# CW308T_LPC1343_CONN.net
KiCad netlist of a schematic drawn in Altium Designer
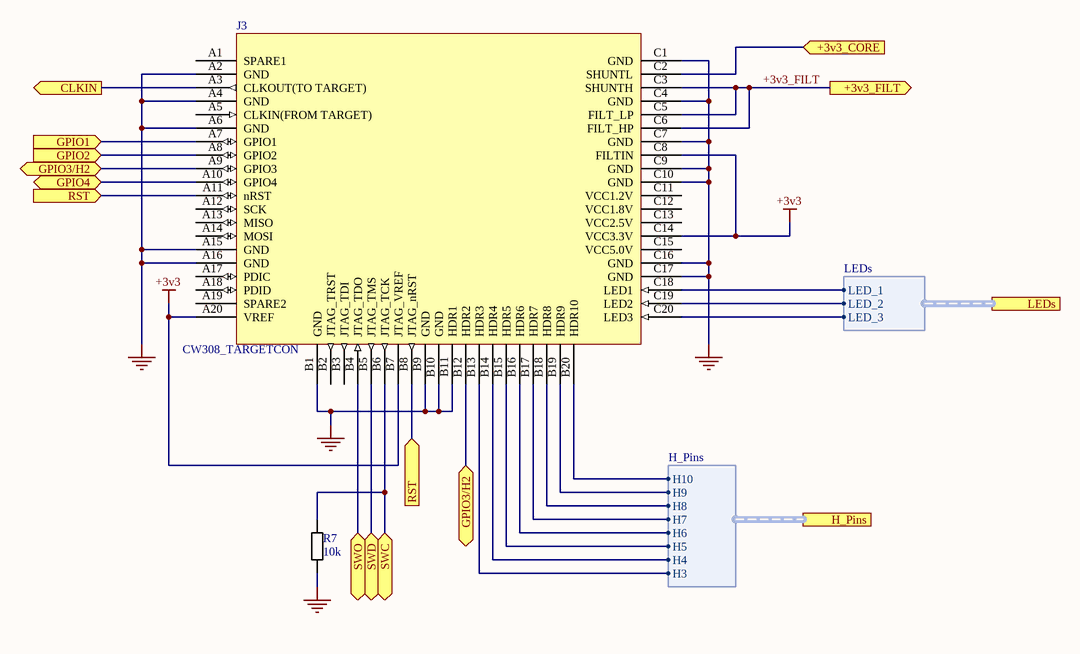
[diagram p0: CW308T_LPC1343_CONN.SchDoc]

(export (version "E")
  (design (tool "Eeschema 10.0.6"))
  (components
    (comp (ref "J3")
      (value "CW308_TARGETCON")
      (footprint "CW308_TBOARD_CONN")
      (description "CW308 \"Standard\" Target Board Connector")
      (fields (field (name "PART NUMBER") "CW308_TBOARD"))
      (libsource (lib "NewAE_AltiumLib") (part "CW308_TBOARD"))
    )
    (comp (ref "R7")
      (value "10k")
      (footprint "RESC1608X55N")
      (description "10k res, 0603, 1%, 1/10W")
      (fields (field (name "PART NUMBER") "RCHIP-10K-0603") (field (name "TOLERANCE") "1%"))
      (libsource (lib "NewAE_AltiumLib") (part "RES-EU"))
    )
  )
  (nets
    (net (code "3") (name "+3v3") (class "Default")
      (node (ref "J3") (pin "A20") (pinfunction "VREF_A20") (pintype "tri_state"))
      (node (ref "J3") (pin "B7") (pinfunction "JTAG_VREF_B7") (pintype "tri_state"))
      (node (ref "J3") (pin "C14") (pinfunction "VCC3.3V_C14") (pintype "power_in"))
      (node (ref "J3") (pin "C8") (pinfunction "FILTIN_C8") (pintype "passive"))
    )
    (net (code "4") (name "/+3v3_CORE") (class "Default")
      (node (ref "J3") (pin "C2") (pinfunction "SHUNTL_C2") (pintype "passive"))
    )
    (net (code "5") (name "/+3v3_FILT") (class "Default")
      (node (ref "J3") (pin "C3") (pinfunction "SHUNTH_C3") (pintype "passive"))
      (node (ref "J3") (pin "C5") (pinfunction "FILT_LP_C5") (pintype "passive"))
      (node (ref "J3") (pin "C6") (pinfunction "FILT_HP_C6") (pintype "passive"))
    )
    (net (code "6") (name "/CLKIN") (class "Default")
      (node (ref "J3") (pin "A3") (pinfunction "CLKOUT(TO_TARGET)_A3") (pintype "output"))
    )
    (net (code "7") (name "/GPIO1") (class "Default")
      (node (ref "J3") (pin "A7") (pinfunction "GPIO1_A7") (pintype "bidirectional"))
    )
    (net (code "8") (name "/GPIO2") (class "Default")
      (node (ref "J3") (pin "A8") (pinfunction "GPIO2_A8") (pintype "bidirectional"))
    )
    (net (code "9") (name "/GPIO3{slash}H2") (class "Default")
      (node (ref "J3") (pin "A9") (pinfunction "GPIO3_A9") (pintype "bidirectional"))
      (node (ref "J3") (pin "B12") (pinfunction "HDR2_B12") (pintype "passive"))
    )
    (net (code "10") (name "/GPIO4") (class "Default")
      (node (ref "J3") (pin "A10") (pinfunction "GPIO4_A10") (pintype "bidirectional"))
    )
    (net (code "11") (name "/H3") (class "Default")
      (node (ref "J3") (pin "B13") (pinfunction "HDR3_B13") (pintype "passive"))
    )
    (net (code "12") (name "/H4") (class "Default")
      (node (ref "J3") (pin "B14") (pinfunction "HDR4_B14") (pintype "passive"))
    )
    (net (code "13") (name "/H5") (class "Default")
      (node (ref "J3") (pin "B15") (pinfunction "HDR5_B15") (pintype "passive"))
    )
    (net (code "14") (name "/H6") (class "Default")
      (node (ref "J3") (pin "B16") (pinfunction "HDR6_B16") (pintype "passive"))
    )
    (net (code "15") (name "/H7") (class "Default")
      (node (ref "J3") (pin "B17") (pinfunction "HDR7_B17") (pintype "passive"))
    )
    (net (code "16") (name "/H8") (class "Default")
      (node (ref "J3") (pin "B18") (pinfunction "HDR8_B18") (pintype "passive"))
    )
    (net (code "17") (name "/H9") (class "Default")
      (node (ref "J3") (pin "B19") (pinfunction "HDR9_B19") (pintype "passive"))
    )
    (net (code "18") (name "/H10") (class "Default")
      (node (ref "J3") (pin "B20") (pinfunction "HDR10_B20") (pintype "passive"))
    )
    (net (code "19") (name "/LED_1") (class "Default")
      (node (ref "J3") (pin "C18") (pinfunction "LED1_C18") (pintype "input"))
    )
    (net (code "20") (name "/LED_2") (class "Default")
      (node (ref "J3") (pin "C19") (pinfunction "LED2_C19") (pintype "input"))
    )
    (net (code "21") (name "/LED_3") (class "Default")
      (node (ref "J3") (pin "C20") (pinfunction "LED3_C20") (pintype "input"))
    )
    (net (code "22") (name "/RST") (class "Default")
      (node (ref "J3") (pin "A11") (pinfunction "nRST_A11") (pintype "bidirectional"))
      (node (ref "J3") (pin "B8") (pinfunction "JTAG_nRST_B8") (pintype "output"))
    )
    (net (code "23") (name "/SWC") (class "Default")
      (node (ref "J3") (pin "B6") (pinfunction "JTAG_TCK_B6") (pintype "output"))
      (node (ref "R7") (pin "1") (pinfunction "1_1") (pintype "passive"))
    )
    (net (code "24") (name "/SWD") (class "Default")
      (node (ref "J3") (pin "B5") (pinfunction "JTAG_TMS_B5") (pintype "output"))
    )
    (net (code "25") (name "/SWO") (class "Default")
      (node (ref "J3") (pin "B4") (pinfunction "JTAG_TDO_B4") (pintype "input"))
    )
    (net (code "28") (name "GND") (class "Default")
      (node (ref "J3") (pin "A15") (pinfunction "GND_A15") (pintype "passive"))
      (node (ref "J3") (pin "A16") (pinfunction "GND_A16") (pintype "passive"))
      (node (ref "J3") (pin "A2") (pinfunction "GND_A2") (pintype "passive"))
      (node (ref "J3") (pin "A4") (pinfunction "GND_A4") (pintype "passive"))
      (node (ref "J3") (pin "A6") (pinfunction "GND_A6") (pintype "power_in"))
      (node (ref "J3") (pin "B1") (pinfunction "GND_B1") (pintype "passive"))
      (node (ref "J3") (pin "B10") (pinfunction "GND_B10") (pintype "passive"))
      (node (ref "J3") (pin "B11") (pinfunction "HDR1_B11") (pintype "passive"))
      (node (ref "J3") (pin "B9") (pinfunction "GND_B9") (pintype "passive"))
      (node (ref "J3") (pin "C1") (pinfunction "GND_C1") (pintype "power_in"))
      (node (ref "J3") (pin "C10") (pinfunction "GND_C10") (pintype "power_in"))
      (node (ref "J3") (pin "C16") (pinfunction "GND_C16") (pintype "power_in"))
      (node (ref "J3") (pin "C17") (pinfunction "GND_C17") (pintype "power_in"))
      (node (ref "J3") (pin "C4") (pinfunction "GND_C4") (pintype "power_in"))
      (node (ref "J3") (pin "C7") (pinfunction "GND_C7") (pintype "power_in"))
      (node (ref "J3") (pin "C9") (pinfunction "GND_C9") (pintype "power_in"))
      (node (ref "R7") (pin "2") (pinfunction "2_2") (pintype "passive"))
    )
    (net (code "29") (name "unconnected-(J3-CLKIN(FROM_TARGET)-PadA5)") (class "Default")
      (node (ref "J3") (pin "A5") (pinfunction "CLKIN(FROM_TARGET)_A5") (pintype "input"))
    )
    (net (code "30") (name "unconnected-(J3-JTAG_TDI-PadB3)") (class "Default")
      (node (ref "J3") (pin "B3") (pinfunction "JTAG_TDI_B3") (pintype "output"))
    )
    (net (code "31") (name "unconnected-(J3-JTAG_TRST-PadB2)") (class "Default")
      (node (ref "J3") (pin "B2") (pinfunction "JTAG_TRST_B2") (pintype "output"))
    )
    (net (code "32") (name "unconnected-(J3-MISO-PadA13)") (class "Default")
      (node (ref "J3") (pin "A13") (pinfunction "MISO_A13") (pintype "bidirectional"))
    )
    (net (code "33") (name "unconnected-(J3-MOSI-PadA14)") (class "Default")
      (node (ref "J3") (pin "A14") (pinfunction "MOSI_A14") (pintype "bidirectional"))
    )
    (net (code "34") (name "unconnected-(J3-PDIC-PadA17)") (class "Default")
      (node (ref "J3") (pin "A17") (pinfunction "PDIC_A17") (pintype "bidirectional"))
    )
    (net (code "35") (name "unconnected-(J3-PDID-PadA18)") (class "Default")
      (node (ref "J3") (pin "A18") (pinfunction "PDID_A18") (pintype "bidirectional"))
    )
    (net (code "36") (name "unconnected-(J3-SCK-PadA12)") (class "Default")
      (node (ref "J3") (pin "A12") (pinfunction "SCK_A12") (pintype "bidirectional"))
    )
    (net (code "37") (name "unconnected-(J3-SPARE1-PadA1)") (class "Default")
      (node (ref "J3") (pin "A1") (pinfunction "SPARE1_A1") (pintype "passive"))
    )
    (net (code "38") (name "unconnected-(J3-SPARE2-PadA19)") (class "Default")
      (node (ref "J3") (pin "A19") (pinfunction "SPARE2_A19") (pintype "passive"))
    )
    (net (code "39") (name "unconnected-(J3-VCC1.2V-PadC11)") (class "Default")
      (node (ref "J3") (pin "C11") (pinfunction "VCC1.2V_C11") (pintype "power_in"))
    )
    (net (code "40") (name "unconnected-(J3-VCC1.8V-PadC12)") (class "Default")
      (node (ref "J3") (pin "C12") (pinfunction "VCC1.8V_C12") (pintype "power_in"))
    )
    (net (code "41") (name "unconnected-(J3-VCC2.5V-PadC13)") (class "Default")
      (node (ref "J3") (pin "C13") (pinfunction "VCC2.5V_C13") (pintype "power_in"))
    )
    (net (code "42") (name "unconnected-(J3-VCC5.0V-PadC15)") (class "Default")
      (node (ref "J3") (pin "C15") (pinfunction "VCC5.0V_C15") (pintype "power_in"))
    )
  )
)
